# 2_BLE-T3-matrix.net
KiCad netlist of a schematic drawn in Altium Designer
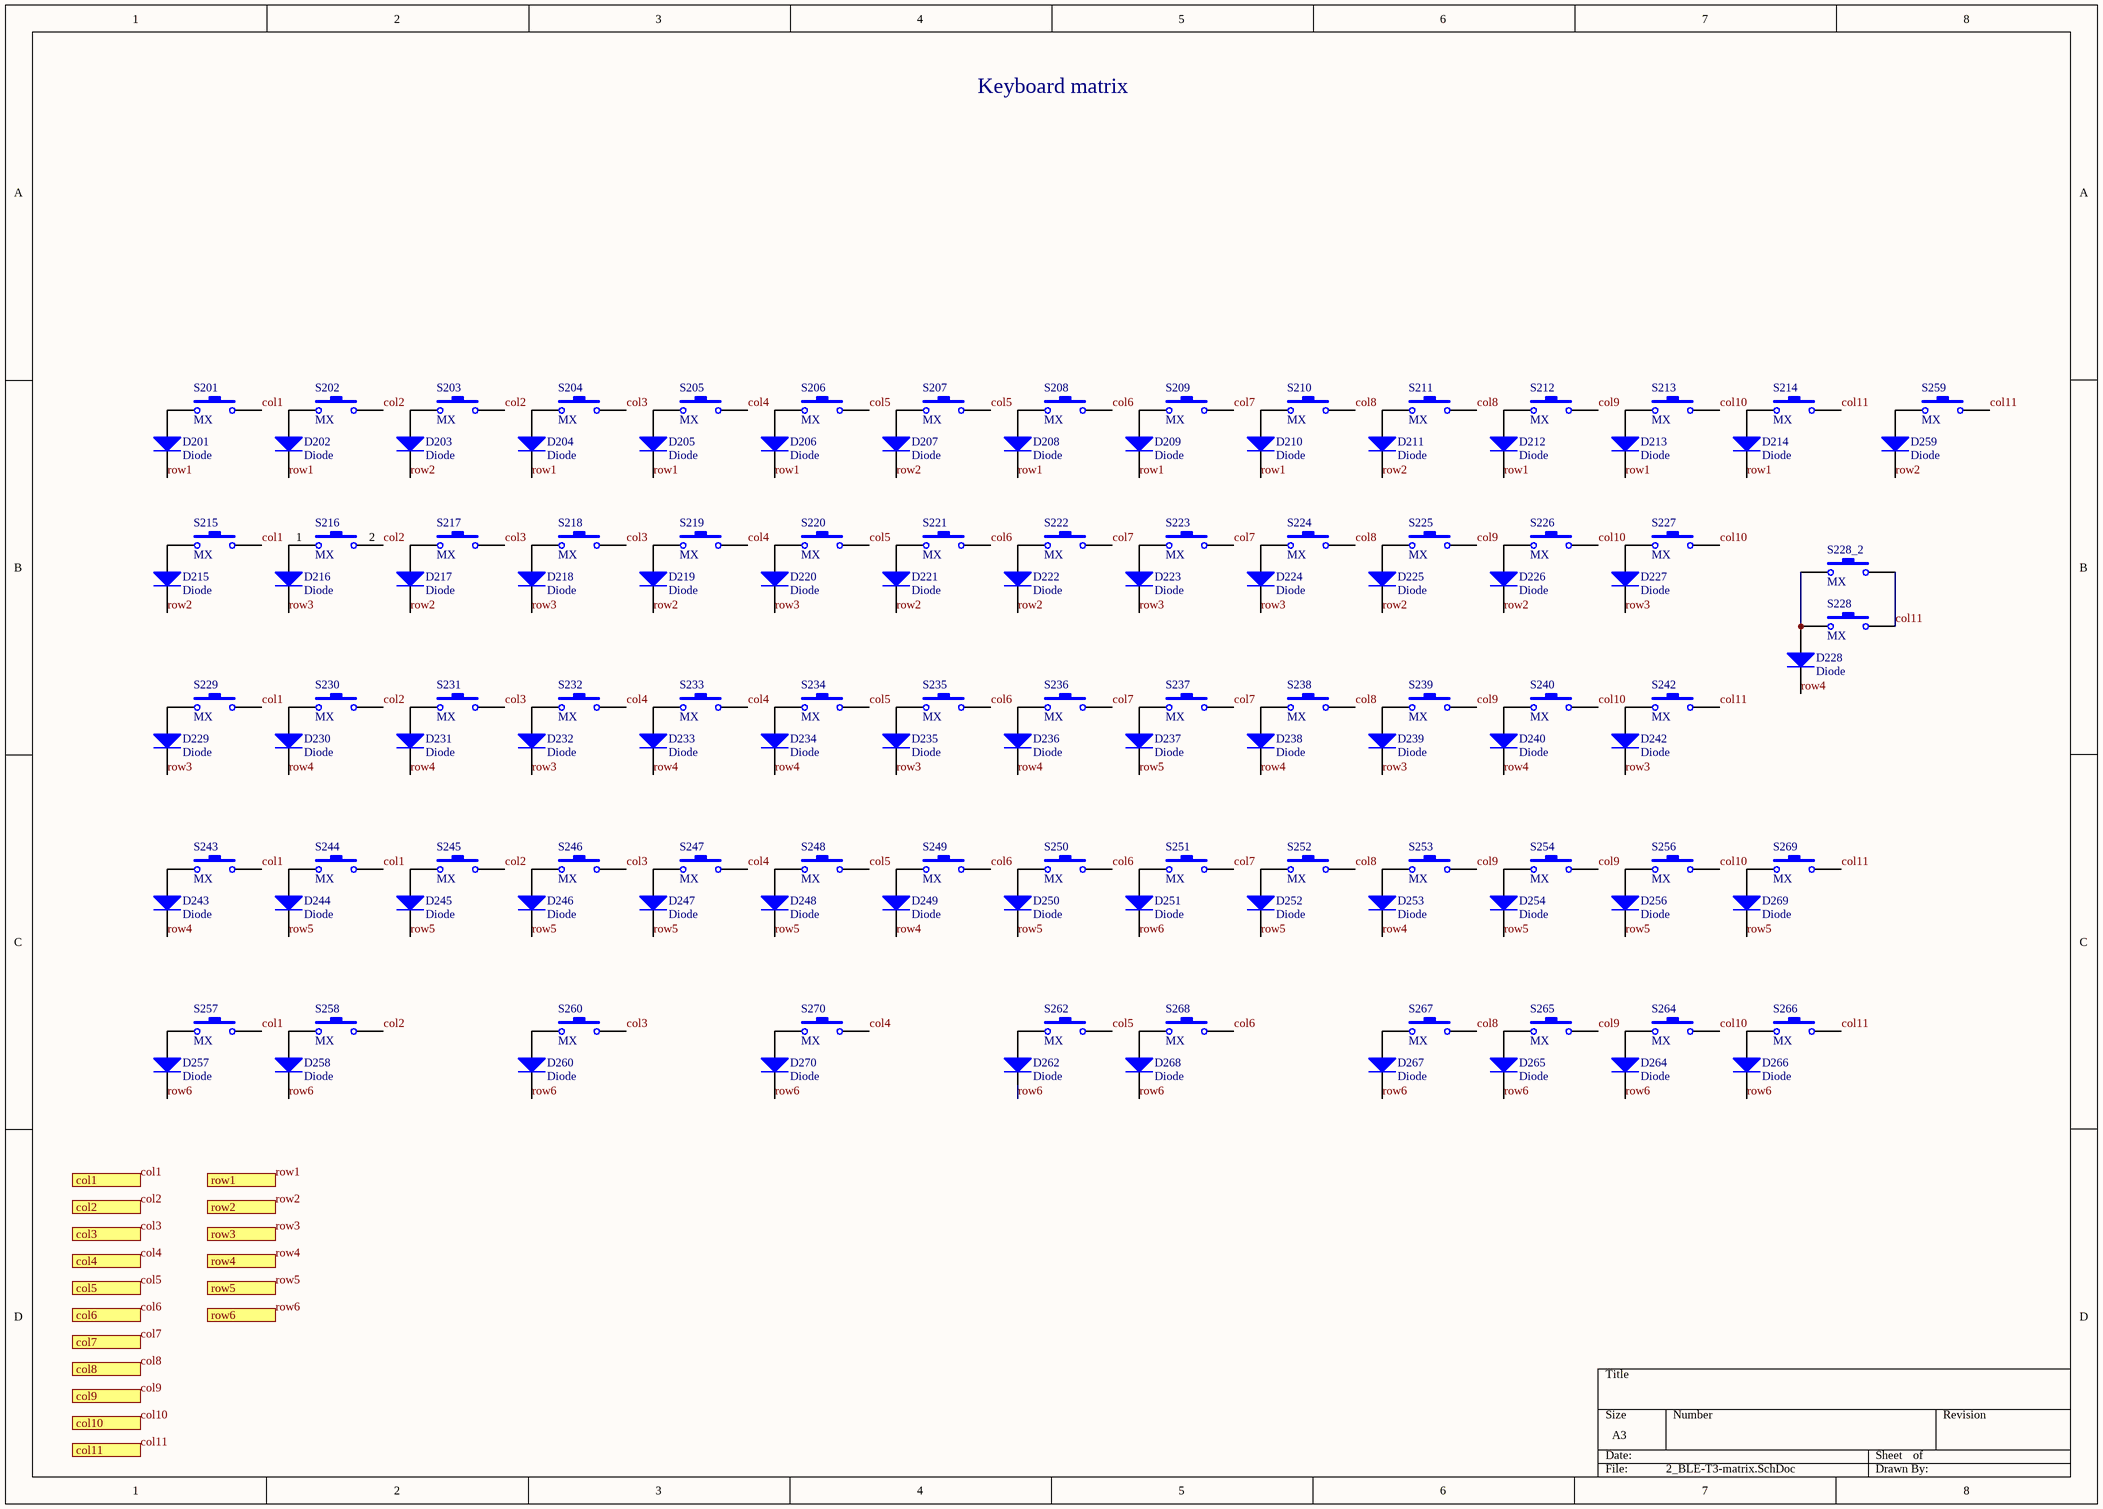
[diagram p0: 2_BLE-T3-matrix.SchDoc]

(export (version "E")
  (design (tool "Eeschema 10.0.6"))
  (components
    (comp (ref "D201")
      (value "Diode")
      (footprint "SOD-123")
      (description "Default Diode")
      (fields (field (name "MFG") "Bourns Inc.") (field (name "LCSC PART #") "C109002"))
      (libsource (lib "Miscellaneous Devices") (part "Diode"))
    )
    (comp (ref "D202")
      (value "Diode")
      (footprint "SOD-123")
      (description "Default Diode")
      (fields (field (name "MFG") "Bourns Inc.") (field (name "LCSC PART #") "C109002"))
      (libsource (lib "Miscellaneous Devices") (part "Diode"))
    )
    (comp (ref "D203")
      (value "Diode")
      (footprint "SOD-123")
      (description "Default Diode")
      (fields (field (name "MFG") "Bourns Inc.") (field (name "LCSC PART #") "C109002"))
      (libsource (lib "Miscellaneous Devices") (part "Diode"))
    )
    (comp (ref "D204")
      (value "Diode")
      (footprint "SOD-123")
      (description "Default Diode")
      (fields (field (name "MFG") "Bourns Inc.") (field (name "LCSC PART #") "C109002"))
      (libsource (lib "Miscellaneous Devices") (part "Diode"))
    )
    (comp (ref "D205")
      (value "Diode")
      (footprint "SOD-123")
      (description "Default Diode")
      (fields (field (name "MFG") "Bourns Inc.") (field (name "LCSC PART #") "C109002"))
      (libsource (lib "Miscellaneous Devices") (part "Diode"))
    )
    (comp (ref "D206")
      (value "Diode")
      (footprint "SOD-123")
      (description "Default Diode")
      (fields (field (name "MFG") "Bourns Inc.") (field (name "LCSC PART #") "C109002"))
      (libsource (lib "Miscellaneous Devices") (part "Diode"))
    )
    (comp (ref "D207")
      (value "Diode")
      (footprint "SOD-123")
      (description "Default Diode")
      (fields (field (name "MFG") "Bourns Inc.") (field (name "LCSC PART #") "C109002"))
      (libsource (lib "Miscellaneous Devices") (part "Diode"))
    )
    (comp (ref "D208")
      (value "Diode")
      (footprint "SOD-123")
      (description "Default Diode")
      (fields (field (name "MFG") "Bourns Inc.") (field (name "LCSC PART #") "C109002"))
      (libsource (lib "Miscellaneous Devices") (part "Diode"))
    )
    (comp (ref "D209")
      (value "Diode")
      (footprint "SOD-123")
      (description "Default Diode")
      (fields (field (name "MFG") "Bourns Inc.") (field (name "LCSC PART #") "C109002"))
      (libsource (lib "Miscellaneous Devices") (part "Diode"))
    )
    (comp (ref "D210")
      (value "Diode")
      (footprint "SOD-123")
      (description "Default Diode")
      (fields (field (name "MFG") "Bourns Inc.") (field (name "LCSC PART #") "C109002"))
      (libsource (lib "Miscellaneous Devices") (part "Diode"))
    )
    (comp (ref "D211")
      (value "Diode")
      (footprint "SOD-123")
      (description "Default Diode")
      (fields (field (name "MFG") "Bourns Inc.") (field (name "LCSC PART #") "C109002"))
      (libsource (lib "Miscellaneous Devices") (part "Diode"))
    )
    (comp (ref "D212")
      (value "Diode")
      (footprint "SOD-123")
      (description "Default Diode")
      (fields (field (name "MFG") "Bourns Inc.") (field (name "LCSC PART #") "C109002"))
      (libsource (lib "Miscellaneous Devices") (part "Diode"))
    )
    (comp (ref "D213")
      (value "Diode")
      (footprint "SOD-123")
      (description "Default Diode")
      (fields (field (name "MFG") "Bourns Inc.") (field (name "LCSC PART #") "C109002"))
      (libsource (lib "Miscellaneous Devices") (part "Diode"))
    )
    (comp (ref "D214")
      (value "Diode")
      (footprint "SOD-123")
      (description "Default Diode")
      (fields (field (name "MFG") "Bourns Inc.") (field (name "LCSC PART #") "C109002"))
      (libsource (lib "Miscellaneous Devices") (part "Diode"))
    )
    (comp (ref "D215")
      (value "Diode")
      (footprint "SOD-123")
      (description "Default Diode")
      (fields (field (name "MFG") "Bourns Inc.") (field (name "LCSC PART #") "C109002"))
      (libsource (lib "Miscellaneous Devices") (part "Diode"))
    )
    (comp (ref "D216")
      (value "Diode")
      (footprint "SOD-123")
      (description "Default Diode")
      (fields (field (name "MFG") "Bourns Inc.") (field (name "LCSC PART #") "C109002"))
      (libsource (lib "Miscellaneous Devices") (part "Diode"))
    )
    (comp (ref "D217")
      (value "Diode")
      (footprint "SOD-123")
      (description "Default Diode")
      (fields (field (name "MFG") "Bourns Inc.") (field (name "LCSC PART #") "C109002"))
      (libsource (lib "Miscellaneous Devices") (part "Diode"))
    )
    (comp (ref "D218")
      (value "Diode")
      (footprint "SOD-123")
      (description "Default Diode")
      (fields (field (name "MFG") "Bourns Inc.") (field (name "LCSC PART #") "C109002"))
      (libsource (lib "Miscellaneous Devices") (part "Diode"))
    )
    (comp (ref "D219")
      (value "Diode")
      (footprint "SOD-123")
      (description "Default Diode")
      (fields (field (name "MFG") "Bourns Inc.") (field (name "LCSC PART #") "C109002"))
      (libsource (lib "Miscellaneous Devices") (part "Diode"))
    )
    (comp (ref "D220")
      (value "Diode")
      (footprint "SOD-123")
      (description "Default Diode")
      (fields (field (name "MFG") "Bourns Inc.") (field (name "LCSC PART #") "C109002"))
      (libsource (lib "Miscellaneous Devices") (part "Diode"))
    )
    (comp (ref "D221")
      (value "Diode")
      (footprint "SOD-123")
      (description "Default Diode")
      (fields (field (name "MFG") "Bourns Inc.") (field (name "LCSC PART #") "C109002"))
      (libsource (lib "Miscellaneous Devices") (part "Diode"))
    )
    (comp (ref "D222")
      (value "Diode")
      (footprint "SOD-123")
      (description "Default Diode")
      (fields (field (name "MFG") "Bourns Inc.") (field (name "LCSC PART #") "C109002"))
      (libsource (lib "Miscellaneous Devices") (part "Diode"))
    )
    (comp (ref "D223")
      (value "Diode")
      (footprint "SOD-123")
      (description "Default Diode")
      (fields (field (name "MFG") "Bourns Inc.") (field (name "LCSC PART #") "C109002"))
      (libsource (lib "Miscellaneous Devices") (part "Diode"))
    )
    (comp (ref "D224")
      (value "Diode")
      (footprint "SOD-123")
      (description "Default Diode")
      (fields (field (name "MFG") "Bourns Inc.") (field (name "LCSC PART #") "C109002"))
      (libsource (lib "Miscellaneous Devices") (part "Diode"))
    )
    (comp (ref "D225")
      (value "Diode")
      (footprint "SOD-123")
      (description "Default Diode")
      (fields (field (name "MFG") "Bourns Inc.") (field (name "LCSC PART #") "C109002"))
      (libsource (lib "Miscellaneous Devices") (part "Diode"))
    )
    (comp (ref "D226")
      (value "Diode")
      (footprint "SOD-123")
      (description "Default Diode")
      (fields (field (name "MFG") "Bourns Inc.") (field (name "LCSC PART #") "C109002"))
      (libsource (lib "Miscellaneous Devices") (part "Diode"))
    )
    (comp (ref "D227")
      (value "Diode")
      (footprint "SOD-123")
      (description "Default Diode")
      (fields (field (name "MFG") "Bourns Inc.") (field (name "LCSC PART #") "C109002"))
      (libsource (lib "Miscellaneous Devices") (part "Diode"))
    )
    (comp (ref "D228")
      (value "Diode")
      (footprint "SOD-123")
      (description "Default Diode")
      (fields (field (name "MFG") "Bourns Inc.") (field (name "LCSC PART #") "C109002"))
      (libsource (lib "Miscellaneous Devices") (part "Diode"))
    )
    (comp (ref "D229")
      (value "Diode")
      (footprint "SOD-123")
      (description "Default Diode")
      (fields (field (name "MFG") "Bourns Inc.") (field (name "LCSC PART #") "C109002"))
      (libsource (lib "Miscellaneous Devices") (part "Diode"))
    )
    (comp (ref "D230")
      (value "Diode")
      (footprint "SOD-123")
      (description "Default Diode")
      (fields (field (name "MFG") "Bourns Inc.") (field (name "LCSC PART #") "C109002"))
      (libsource (lib "Miscellaneous Devices") (part "Diode"))
    )
    (comp (ref "D231")
      (value "Diode")
      (footprint "SOD-123")
      (description "Default Diode")
      (fields (field (name "MFG") "Bourns Inc.") (field (name "LCSC PART #") "C109002"))
      (libsource (lib "Miscellaneous Devices") (part "Diode"))
    )
    (comp (ref "D232")
      (value "Diode")
      (footprint "SOD-123")
      (description "Default Diode")
      (fields (field (name "MFG") "Bourns Inc.") (field (name "LCSC PART #") "C109002"))
      (libsource (lib "Miscellaneous Devices") (part "Diode"))
    )
    (comp (ref "D233")
      (value "Diode")
      (footprint "SOD-123")
      (description "Default Diode")
      (fields (field (name "MFG") "Bourns Inc.") (field (name "LCSC PART #") "C109002"))
      (libsource (lib "Miscellaneous Devices") (part "Diode"))
    )
    (comp (ref "D234")
      (value "Diode")
      (footprint "SOD-123")
      (description "Default Diode")
      (fields (field (name "MFG") "Bourns Inc.") (field (name "LCSC PART #") "C109002"))
      (libsource (lib "Miscellaneous Devices") (part "Diode"))
    )
    (comp (ref "D235")
      (value "Diode")
      (footprint "SOD-123")
      (description "Default Diode")
      (fields (field (name "MFG") "Bourns Inc.") (field (name "LCSC PART #") "C109002"))
      (libsource (lib "Miscellaneous Devices") (part "Diode"))
    )
    (comp (ref "D236")
      (value "Diode")
      (footprint "SOD-123")
      (description "Default Diode")
      (fields (field (name "MFG") "Bourns Inc.") (field (name "LCSC PART #") "C109002"))
      (libsource (lib "Miscellaneous Devices") (part "Diode"))
    )
    (comp (ref "D237")
      (value "Diode")
      (footprint "SOD-123")
      (description "Default Diode")
      (fields (field (name "MFG") "Bourns Inc.") (field (name "LCSC PART #") "C109002"))
      (libsource (lib "Miscellaneous Devices") (part "Diode"))
    )
    (comp (ref "D238")
      (value "Diode")
      (footprint "SOD-123")
      (description "Default Diode")
      (fields (field (name "MFG") "Bourns Inc.") (field (name "LCSC PART #") "C109002"))
      (libsource (lib "Miscellaneous Devices") (part "Diode"))
    )
    (comp (ref "D239")
      (value "Diode")
      (footprint "SOD-123")
      (description "Default Diode")
      (fields (field (name "MFG") "Bourns Inc.") (field (name "LCSC PART #") "C109002"))
      (libsource (lib "Miscellaneous Devices") (part "Diode"))
    )
    (comp (ref "D240")
      (value "Diode")
      (footprint "SOD-123")
      (description "Default Diode")
      (fields (field (name "MFG") "Bourns Inc.") (field (name "LCSC PART #") "C109002"))
      (libsource (lib "Miscellaneous Devices") (part "Diode"))
    )
    (comp (ref "D242")
      (value "Diode")
      (footprint "SOD-123")
      (description "Default Diode")
      (fields (field (name "MFG") "Bourns Inc.") (field (name "LCSC PART #") "C109002"))
      (libsource (lib "Miscellaneous Devices") (part "Diode"))
    )
    (comp (ref "D243")
      (value "Diode")
      (footprint "SOD-123")
      (description "Default Diode")
      (fields (field (name "MFG") "Bourns Inc.") (field (name "LCSC PART #") "C109002"))
      (libsource (lib "Miscellaneous Devices") (part "Diode"))
    )
    (comp (ref "D244")
      (value "Diode")
      (footprint "SOD-123")
      (description "Default Diode")
      (fields (field (name "MFG") "Bourns Inc.") (field (name "LCSC PART #") "C109002"))
      (libsource (lib "Miscellaneous Devices") (part "Diode"))
    )
    (comp (ref "D245")
      (value "Diode")
      (footprint "SOD-123")
      (description "Default Diode")
      (fields (field (name "MFG") "Bourns Inc.") (field (name "LCSC PART #") "C109002"))
      (libsource (lib "Miscellaneous Devices") (part "Diode"))
    )
    (comp (ref "D246")
      (value "Diode")
      (footprint "SOD-123")
      (description "Default Diode")
      (fields (field (name "MFG") "Bourns Inc.") (field (name "LCSC PART #") "C109002"))
      (libsource (lib "Miscellaneous Devices") (part "Diode"))
    )
    (comp (ref "D247")
      (value "Diode")
      (footprint "SOD-123")
      (description "Default Diode")
      (fields (field (name "MFG") "Bourns Inc.") (field (name "LCSC PART #") "C109002"))
      (libsource (lib "Miscellaneous Devices") (part "Diode"))
    )
    (comp (ref "D248")
      (value "Diode")
      (footprint "SOD-123")
      (description "Default Diode")
      (fields (field (name "MFG") "Bourns Inc.") (field (name "LCSC PART #") "C109002"))
      (libsource (lib "Miscellaneous Devices") (part "Diode"))
    )
    (comp (ref "D249")
      (value "Diode")
      (footprint "SOD-123")
      (description "Default Diode")
      (fields (field (name "MFG") "Bourns Inc.") (field (name "LCSC PART #") "C109002"))
      (libsource (lib "Miscellaneous Devices") (part "Diode"))
    )
    (comp (ref "D250")
      (value "Diode")
      (footprint "SOD-123")
      (description "Default Diode")
      (fields (field (name "MFG") "Bourns Inc.") (field (name "LCSC PART #") "C109002"))
      (libsource (lib "Miscellaneous Devices") (part "Diode"))
    )
    (comp (ref "D251")
      (value "Diode")
      (footprint "SOD-123")
      (description "Default Diode")
      (fields (field (name "MFG") "Bourns Inc.") (field (name "LCSC PART #") "C109002"))
      (libsource (lib "Miscellaneous Devices") (part "Diode"))
    )
    (comp (ref "D252")
      (value "Diode")
      (footprint "SOD-123")
      (description "Default Diode")
      (fields (field (name "MFG") "Bourns Inc.") (field (name "LCSC PART #") "C109002"))
      (libsource (lib "Miscellaneous Devices") (part "Diode"))
    )
    (comp (ref "D253")
      (value "Diode")
      (footprint "SOD-123")
      (description "Default Diode")
      (fields (field (name "MFG") "Bourns Inc.") (field (name "LCSC PART #") "C109002"))
      (libsource (lib "Miscellaneous Devices") (part "Diode"))
    )
    (comp (ref "D254")
      (value "Diode")
      (footprint "SOD-123")
      (description "Default Diode")
      (fields (field (name "MFG") "Bourns Inc.") (field (name "LCSC PART #") "C109002"))
      (libsource (lib "Miscellaneous Devices") (part "Diode"))
    )
    (comp (ref "D256")
      (value "Diode")
      (footprint "SOD-123")
      (description "Default Diode")
      (fields (field (name "MFG") "Bourns Inc.") (field (name "LCSC PART #") "C109002"))
      (libsource (lib "Miscellaneous Devices") (part "Diode"))
    )
    (comp (ref "D257")
      (value "Diode")
      (footprint "SOD-123")
      (description "Default Diode")
      (fields (field (name "MFG") "Bourns Inc.") (field (name "LCSC PART #") "C109002"))
      (libsource (lib "Miscellaneous Devices") (part "Diode"))
    )
    (comp (ref "D258")
      (value "Diode")
      (footprint "SOD-123")
      (description "Default Diode")
      (fields (field (name "MFG") "Bourns Inc.") (field (name "LCSC PART #") "C109002"))
      (libsource (lib "Miscellaneous Devices") (part "Diode"))
    )
    (comp (ref "D259")
      (value "Diode")
      (footprint "SOD-123")
      (description "Default Diode")
      (fields (field (name "MFG") "Bourns Inc.") (field (name "LCSC PART #") "C109002"))
      (libsource (lib "Miscellaneous Devices") (part "Diode"))
    )
    (comp (ref "D260")
      (value "Diode")
      (footprint "SOD-123")
      (description "Default Diode")
      (fields (field (name "MFG") "Bourns Inc.") (field (name "LCSC PART #") "C109002"))
      (libsource (lib "Miscellaneous Devices") (part "Diode"))
    )
    (comp (ref "D262")
      (value "Diode")
      (footprint "SOD-123")
      (description "Default Diode")
      (fields (field (name "MFG") "Bourns Inc.") (field (name "LCSC PART #") "C109002"))
      (libsource (lib "Miscellaneous Devices") (part "Diode"))
    )
    (comp (ref "D264")
      (value "Diode")
      (footprint "SOD-123")
      (description "Default Diode")
      (fields (field (name "MFG") "Bourns Inc.") (field (name "LCSC PART #") "C109002"))
      (libsource (lib "Miscellaneous Devices") (part "Diode"))
    )
    (comp (ref "D265")
      (value "Diode")
      (footprint "SOD-123")
      (description "Default Diode")
      (fields (field (name "MFG") "Bourns Inc.") (field (name "LCSC PART #") "C109002"))
      (libsource (lib "Miscellaneous Devices") (part "Diode"))
    )
    (comp (ref "D266")
      (value "Diode")
      (footprint "SOD-123")
      (description "Default Diode")
      (fields (field (name "MFG") "Bourns Inc.") (field (name "LCSC PART #") "C109002"))
      (libsource (lib "Miscellaneous Devices") (part "Diode"))
    )
    (comp (ref "D267")
      (value "Diode")
      (footprint "SOD-123")
      (description "Default Diode")
      (fields (field (name "MFG") "Bourns Inc.") (field (name "LCSC PART #") "C109002"))
      (libsource (lib "Miscellaneous Devices") (part "Diode"))
    )
    (comp (ref "D268")
      (value "Diode")
      (footprint "SOD-123")
      (description "Default Diode")
      (fields (field (name "MFG") "Bourns Inc.") (field (name "LCSC PART #") "C109002"))
      (libsource (lib "Miscellaneous Devices") (part "Diode"))
    )
    (comp (ref "D269")
      (value "Diode")
      (footprint "SOD-123")
      (description "Default Diode")
      (fields (field (name "MFG") "Bourns Inc.") (field (name "LCSC PART #") "C109002"))
      (libsource (lib "Miscellaneous Devices") (part "Diode"))
    )
    (comp (ref "D270")
      (value "Diode")
      (footprint "SOD-123")
      (description "Default Diode")
      (fields (field (name "MFG") "Bourns Inc.") (field (name "LCSC PART #") "C109002"))
      (libsource (lib "Miscellaneous Devices") (part "Diode"))
    )
    (comp (ref "S201")
      (value "MX")
      (footprint "MX-switch - switched pol")
      (description "Switch")
      (libsource (lib "Miscellaneous Devices") (part "SW-PB"))
    )
    (comp (ref "S202")
      (value "MX")
      (footprint "MX-switch - switched pol - connector")
      (description "Switch")
      (libsource (lib "Miscellaneous Devices") (part "SW-PB"))
    )
    (comp (ref "S203")
      (value "MX")
      (footprint "MX-switch - switched pol")
      (description "Switch")
      (libsource (lib "Miscellaneous Devices") (part "SW-PB"))
    )
    (comp (ref "S204")
      (value "MX")
      (footprint "MX-switch")
      (description "Switch")
      (libsource (lib "Miscellaneous Devices") (part "SW-PB"))
    )
    (comp (ref "S205")
      (value "MX")
      (footprint "MX-switch - switched pol")
      (description "Switch")
      (libsource (lib "Miscellaneous Devices") (part "SW-PB"))
    )
    (comp (ref "S206")
      (value "MX")
      (footprint "MX-switch - switched pol")
      (description "Switch")
      (libsource (lib "Miscellaneous Devices") (part "SW-PB"))
    )
    (comp (ref "S207")
      (value "MX")
      (footprint "MX-switch - switched pol")
      (description "Switch")
      (libsource (lib "Miscellaneous Devices") (part "SW-PB"))
    )
    (comp (ref "S208")
      (value "MX")
      (footprint "MX-switch - switched pol")
      (description "Switch")
      (libsource (lib "Miscellaneous Devices") (part "SW-PB"))
    )
    (comp (ref "S209")
      (value "MX")
      (footprint "MX-switch - switched pol")
      (description "Switch")
      (libsource (lib "Miscellaneous Devices") (part "SW-PB"))
    )
    (comp (ref "S210")
      (value "MX")
      (footprint "MX-switch - switched pol")
      (description "Switch")
      (libsource (lib "Miscellaneous Devices") (part "SW-PB"))
    )
    (comp (ref "S211")
      (value "MX")
      (footprint "MX-switch - switched pol")
      (description "Switch")
      (libsource (lib "Miscellaneous Devices") (part "SW-PB"))
    )
    (comp (ref "S212")
      (value "MX")
      (footprint "MX-switch - switched pol")
      (description "Switch")
      (libsource (lib "Miscellaneous Devices") (part "SW-PB"))
    )
    (comp (ref "S213")
      (value "MX")
      (footprint "MX-switch - switched pol")
      (description "Switch")
      (libsource (lib "Miscellaneous Devices") (part "SW-PB"))
    )
    (comp (ref "S214")
      (value "MX")
      (footprint "MX-switch - switched pol")
      (description "Switch")
      (libsource (lib "Miscellaneous Devices") (part "SW-PB"))
    )
    (comp (ref "S215")
      (value "MX")
      (footprint "MX-switch - 1.5U - switched pol")
      (description "TAB")
      (libsource (lib "Miscellaneous Devices") (part "SW-PB"))
    )
    (comp (ref "S216")
      (value "MX")
      (footprint "MX-switch - switched pol")
      (description "Switch")
      (libsource (lib "") (part "SW-PB_1"))
    )
    (comp (ref "S217")
      (value "MX")
      (footprint "MX-switch - switched pol")
      (description "Switch")
      (libsource (lib "Miscellaneous Devices") (part "SW-PB"))
    )
    (comp (ref "S218")
      (value "MX")
      (footprint "MX-switch - switched pol")
      (description "Switch")
      (libsource (lib "Miscellaneous Devices") (part "SW-PB"))
    )
    (comp (ref "S219")
      (value "MX")
      (footprint "MX-switch - switched pol")
      (description "Switch")
      (libsource (lib "Miscellaneous Devices") (part "SW-PB"))
    )
    (comp (ref "S220")
      (value "MX")
      (footprint "MX-switch")
      (description "Switch")
      (libsource (lib "Miscellaneous Devices") (part "SW-PB"))
    )
    (comp (ref "S221")
      (value "MX")
      (footprint "MX-switch - switched pol")
      (description "Switch")
      (libsource (lib "Miscellaneous Devices") (part "SW-PB"))
    )
    (comp (ref "S222")
      (value "MX")
      (footprint "MX-switch - switched pol")
      (description "Switch")
      (libsource (lib "Miscellaneous Devices") (part "SW-PB"))
    )
    (comp (ref "S223")
      (value "MX")
      (footprint "MX-switch - switched pol")
      (description "Switch")
      (libsource (lib "Miscellaneous Devices") (part "SW-PB"))
    )
    (comp (ref "S224")
      (value "MX")
      (footprint "MX-switch - switched pol")
      (description "Switch")
      (libsource (lib "Miscellaneous Devices") (part "SW-PB"))
    )
    (comp (ref "S225")
      (value "MX")
      (footprint "MX-switch - switched pol")
      (description "Switch")
      (libsource (lib "Miscellaneous Devices") (part "SW-PB"))
    )
    (comp (ref "S226")
      (value "MX")
      (footprint "MX-switch")
      (description "Switch")
      (libsource (lib "Miscellaneous Devices") (part "SW-PB"))
    )
    (comp (ref "S227")
      (value "MX")
      (footprint "MX-switch")
      (description "Switch")
      (libsource (lib "Miscellaneous Devices") (part "SW-PB"))
    )
    (comp (ref "S228")
      (value "MX")
      (footprint "MX-switch - 1.5U")
      (description "Switch")
      (libsource (lib "Miscellaneous Devices") (part "SW-PB"))
    )
    (comp (ref "S228_2")
      (value "MX")
      (footprint "MX-switch")
      (description "Switch")
      (libsource (lib "Miscellaneous Devices") (part "SW-PB"))
    )
    (comp (ref "S229")
      (value "MX")
      (footprint "MX-switch - CAPS")
      (description "Switch")
      (libsource (lib "Miscellaneous Devices") (part "SW-PB"))
    )
    (comp (ref "S230")
      (value "MX")
      (footprint "MX-switch - switched pol")
      (description "Switch")
      (libsource (lib "Miscellaneous Devices") (part "SW-PB"))
    )
    (comp (ref "S231")
      (value "MX")
      (footprint "MX-switch - switched pol")
      (description "Switch")
      (libsource (lib "Miscellaneous Devices") (part "SW-PB"))
    )
    (comp (ref "S232")
      (value "MX")
      (footprint "MX-switch - switched pol")
      (description "Switch")
      (libsource (lib "Miscellaneous Devices") (part "SW-PB"))
    )
    (comp (ref "S233")
      (value "MX")
      (footprint "MX-switch - switched pol")
      (description "Switch")
      (libsource (lib "Miscellaneous Devices") (part "SW-PB"))
    )
    (comp (ref "S234")
      (value "MX")
      (footprint "MX-switch")
      (description "Switch")
      (libsource (lib "Miscellaneous Devices") (part "SW-PB"))
    )
    (comp (ref "S235")
      (value "MX")
      (footprint "MX-switch - switched pol")
      (description "Switch")
      (libsource (lib "Miscellaneous Devices") (part "SW-PB"))
    )
    (comp (ref "S236")
      (value "MX")
      (footprint "MX-switch - switched pol")
      (description "Switch")
      (libsource (lib "Miscellaneous Devices") (part "SW-PB"))
    )
    (comp (ref "S237")
      (value "MX")
      (footprint "MX-switch - switched pol")
      (description "Switch")
      (libsource (lib "Miscellaneous Devices") (part "SW-PB"))
    )
    (comp (ref "S238")
      (value "MX")
      (footprint "MX-switch - switched pol")
      (description "Switch")
      (libsource (lib "Miscellaneous Devices") (part "SW-PB"))
    )
    (comp (ref "S239")
      (value "MX")
      (footprint "MX-switch")
      (description "Switch")
      (libsource (lib "Miscellaneous Devices") (part "SW-PB"))
    )
    (comp (ref "S240")
      (value "MX")
      (footprint "MX-switch - switched pol")
      (description "Switch")
      (libsource (lib "Miscellaneous Devices") (part "SW-PB"))
    )
    (comp (ref "S242")
      (value "MX")
      (footprint "MX-switch - Enter")
      (description "Switch")
      (libsource (lib "Miscellaneous Devices") (part "SW-PB"))
    )
    (comp (ref "S243")
      (value "MX")
      (footprint "MX-switch - Left shift")
      (description "Switch")
      (libsource (lib "Miscellaneous Devices") (part "SW-PB"))
    )
    (comp (ref "S244")
      (value "MX")
      (footprint "MX-switch - switched pol")
      (description "Switch")
      (libsource (lib "Miscellaneous Devices") (part "SW-PB"))
    )
    (comp (ref "S245")
      (value "MX")
      (footprint "MX-switch - switched pol")
      (description "Switch")
      (libsource (lib "Miscellaneous Devices") (part "SW-PB"))
    )
    (comp (ref "S246")
      (value "MX")
      (footprint "MX-switch - switched pol")
      (description "Switch")
      (libsource (lib "Miscellaneous Devices") (part "SW-PB"))
    )
    (comp (ref "S247")
      (value "MX")
      (footprint "MX-switch - switched pol")
      (description "Switch")
      (libsource (lib "Miscellaneous Devices") (part "SW-PB"))
    )
    (comp (ref "S248")
      (value "MX")
      (footprint "MX-switch")
      (description "Switch")
      (libsource (lib "Miscellaneous Devices") (part "SW-PB"))
    )
    (comp (ref "S249")
      (value "MX")
      (footprint "MX-switch - switched pol")
      (description "Switch")
      (libsource (lib "Miscellaneous Devices") (part "SW-PB"))
    )
    (comp (ref "S250")
      (value "MX")
      (footprint "MX-switch - switched pol")
      (description "Switch")
      (libsource (lib "Miscellaneous Devices") (part "SW-PB"))
    )
    (comp (ref "S251")
      (value "MX")
      (footprint "MX-switch - switched pol")
      (description "Switch")
      (libsource (lib "Miscellaneous Devices") (part "SW-PB"))
    )
    (comp (ref "S252")
      (value "MX")
      (footprint "MX-switch - switched pol")
      (description "Switch")
      (libsource (lib "Miscellaneous Devices") (part "SW-PB"))
    )
    (comp (ref "S253")
      (value "MX")
      (footprint "MX-switch - switched pol")
      (description "Switch")
      (libsource (lib "Miscellaneous Devices") (part "SW-PB"))
    )
    (comp (ref "S254")
      (value "MX")
      (footprint "MX-switch - switched pol")
      (description "Switch")
      (libsource (lib "Miscellaneous Devices") (part "SW-PB"))
    )
    (comp (ref "S256")
      (value "MX")
      (footprint "MX-switch - right shift")
      (description "Switch")
      (libsource (lib "Miscellaneous Devices") (part "SW-PB"))
    )
    (comp (ref "S257")
      (value "MX")
      (footprint "MX-switch - 1.5u MOD-L")
      (description "Switch")
      (libsource (lib "Miscellaneous Devices") (part "SW-PB"))
    )
    (comp (ref "S258")
      (value "MX")
      (footprint "MX-switch - 1u MOD-L")
      (description "Switch")
      (libsource (lib "Miscellaneous Devices") (part "SW-PB"))
    )
    (comp (ref "S259")
      (value "MX")
      (footprint "MX-switch - backspace")
      (description "Switch")
      (libsource (lib "Miscellaneous Devices") (part "SW-PB"))
    )
    (comp (ref "S260")
      (value "MX")
      (footprint "MX-switch - 1.5u MOD-L")
      (description "Switch")
      (libsource (lib "Miscellaneous Devices") (part "SW-PB"))
    )
    (comp (ref "S262")
      (value "MX")
      (footprint "MX-switch - Space_V3")
      (description "Switch")
      (libsource (lib "Miscellaneous Devices") (part "SW-PB"))
    )
    (comp (ref "S264")
      (value "MX")
      (footprint "MX-switch - 1u MOD-R")
      (description "Switch")
      (libsource (lib "Miscellaneous Devices") (part "SW-PB"))
    )
    (comp (ref "S265")
      (value "MX")
      (footprint "MX-switch - 1.5u MOD-R")
      (description "Switch")
      (libsource (lib "Miscellaneous Devices") (part "SW-PB"))
    )
    (comp (ref "S266")
      (value "MX")
      (footprint "MX-switch - 1.5u MOD-R")
      (description "Switch")
      (libsource (lib "Miscellaneous Devices") (part "SW-PB"))
    )
    (comp (ref "S267")
      (value "MX")
      (footprint "MX-switch - switched pol")
      (description "Switch")
      (libsource (lib "Miscellaneous Devices") (part "SW-PB"))
    )
    (comp (ref "S268")
      (value "MX")
      (footprint "MX-switch - R split space_V2")
      (description "Switch")
      (libsource (lib "Miscellaneous Devices") (part "SW-PB"))
    )
    (comp (ref "S269")
      (value "MX")
      (footprint "MX-switch")
      (description "Switch")
      (libsource (lib "Miscellaneous Devices") (part "SW-PB"))
    )
    (comp (ref "S270")
      (value "MX")
      (footprint "MX-switch - L split space_V2")
      (description "Switch")
      (libsource (lib "Miscellaneous Devices") (part "SW-PB"))
    )
  )
  (nets
    (net (code "1") (name "/col1") (class "Default")
      (node (ref "S201") (pin "2") (pinfunction "2_2") (pintype "passive"))
      (node (ref "S215") (pin "2") (pinfunction "2_2") (pintype "passive"))
      (node (ref "S229") (pin "2") (pinfunction "2_2") (pintype "passive"))
      (node (ref "S243") (pin "2") (pinfunction "2_2") (pintype "passive"))
      (node (ref "S244") (pin "2") (pinfunction "2_2") (pintype "passive"))
      (node (ref "S257") (pin "2") (pinfunction "2_2") (pintype "passive"))
    )
    (net (code "2") (name "/col2") (class "Default")
      (node (ref "S202") (pin "2") (pinfunction "2_2") (pintype "passive"))
      (node (ref "S203") (pin "2") (pinfunction "2_2") (pintype "passive"))
      (node (ref "S216") (pin "2") (pinfunction "2_2") (pintype "passive"))
      (node (ref "S230") (pin "2") (pinfunction "2_2") (pintype "passive"))
      (node (ref "S245") (pin "2") (pinfunction "2_2") (pintype "passive"))
      (node (ref "S258") (pin "2") (pinfunction "2_2") (pintype "passive"))
    )
    (net (code "3") (name "/col3") (class "Default")
      (node (ref "S204") (pin "2") (pinfunction "2_2") (pintype "passive"))
      (node (ref "S217") (pin "2") (pinfunction "2_2") (pintype "passive"))
      (node (ref "S218") (pin "2") (pinfunction "2_2") (pintype "passive"))
      (node (ref "S231") (pin "2") (pinfunction "2_2") (pintype "passive"))
      (node (ref "S246") (pin "2") (pinfunction "2_2") (pintype "passive"))
      (node (ref "S260") (pin "2") (pinfunction "2_2") (pintype "passive"))
    )
    (net (code "4") (name "/col4") (class "Default")
      (node (ref "S205") (pin "2") (pinfunction "2_2") (pintype "passive"))
      (node (ref "S219") (pin "2") (pinfunction "2_2") (pintype "passive"))
      (node (ref "S232") (pin "2") (pinfunction "2_2") (pintype "passive"))
      (node (ref "S233") (pin "2") (pinfunction "2_2") (pintype "passive"))
      (node (ref "S247") (pin "2") (pinfunction "2_2") (pintype "passive"))
      (node (ref "S270") (pin "2") (pinfunction "2_2") (pintype "passive"))
    )
    (net (code "5") (name "/col5") (class "Default")
      (node (ref "S206") (pin "2") (pinfunction "2_2") (pintype "passive"))
      (node (ref "S207") (pin "2") (pinfunction "2_2") (pintype "passive"))
      (node (ref "S220") (pin "2") (pinfunction "2_2") (pintype "passive"))
      (node (ref "S234") (pin "2") (pinfunction "2_2") (pintype "passive"))
      (node (ref "S248") (pin "2") (pinfunction "2_2") (pintype "passive"))
      (node (ref "S262") (pin "1") (pinfunction "1_1") (pintype "passive"))
    )
    (net (code "6") (name "/col6") (class "Default")
      (node (ref "S208") (pin "2") (pinfunction "2_2") (pintype "passive"))
      (node (ref "S221") (pin "2") (pinfunction "2_2") (pintype "passive"))
      (node (ref "S235") (pin "2") (pinfunction "2_2") (pintype "passive"))
      (node (ref "S249") (pin "2") (pinfunction "2_2") (pintype "passive"))
      (node (ref "S250") (pin "2") (pinfunction "2_2") (pintype "passive"))
      (node (ref "S268") (pin "2") (pinfunction "2_2") (pintype "passive"))
    )
    (net (code "7") (name "/col7") (class "Default")
      (node (ref "S209") (pin "2") (pinfunction "2_2") (pintype "passive"))
      (node (ref "S222") (pin "2") (pinfunction "2_2") (pintype "passive"))
      (node (ref "S223") (pin "2") (pinfunction "2_2") (pintype "passive"))
      (node (ref "S236") (pin "2") (pinfunction "2_2") (pintype "passive"))
      (node (ref "S237") (pin "2") (pinfunction "2_2") (pintype "passive"))
      (node (ref "S251") (pin "2") (pinfunction "2_2") (pintype "passive"))
    )
    (net (code "8") (name "/col8") (class "Default")
      (node (ref "S210") (pin "2") (pinfunction "2_2") (pintype "passive"))
      (node (ref "S211") (pin "2") (pinfunction "2_2") (pintype "passive"))
      (node (ref "S224") (pin "2") (pinfunction "2_2") (pintype "passive"))
      (node (ref "S238") (pin "2") (pinfunction "2_2") (pintype "passive"))
      (node (ref "S252") (pin "2") (pinfunction "2_2") (pintype "passive"))
      (node (ref "S267") (pin "2") (pinfunction "2_2") (pintype "passive"))
    )
    (net (code "9") (name "/col9") (class "Default")
      (node (ref "S212") (pin "2") (pinfunction "2_2") (pintype "passive"))
      (node (ref "S225") (pin "2") (pinfunction "2_2") (pintype "passive"))
      (node (ref "S239") (pin "2") (pinfunction "2_2") (pintype "passive"))
      (node (ref "S253") (pin "2") (pinfunction "2_2") (pintype "passive"))
      (node (ref "S254") (pin "2") (pinfunction "2_2") (pintype "passive"))
      (node (ref "S265") (pin "1") (pinfunction "1_1") (pintype "passive"))
    )
    (net (code "10") (name "/col10") (class "Default")
      (node (ref "S213") (pin "2") (pinfunction "2_2") (pintype "passive"))
      (node (ref "S226") (pin "2") (pinfunction "2_2") (pintype "passive"))
      (node (ref "S227") (pin "2") (pinfunction "2_2") (pintype "passive"))
      (node (ref "S240") (pin "2") (pinfunction "2_2") (pintype "passive"))
      (node (ref "S256") (pin "2") (pinfunction "2_2") (pintype "passive"))
      (node (ref "S264") (pin "2") (pinfunction "2_2") (pintype "passive"))
    )
    (net (code "11") (name "/col11") (class "Default")
      (node (ref "S214") (pin "2") (pinfunction "2_2") (pintype "passive"))
      (node (ref "S228") (pin "2") (pinfunction "2_2") (pintype "passive"))
      (node (ref "S228_2") (pin "2") (pinfunction "2_2") (pintype "passive"))
      (node (ref "S242") (pin "2") (pinfunction "2_2") (pintype "passive"))
      (node (ref "S259") (pin "2") (pinfunction "2_2") (pintype "passive"))
      (node (ref "S266") (pin "2") (pinfunction "2_2") (pintype "passive"))
      (node (ref "S269") (pin "2") (pinfunction "2_2") (pintype "passive"))
    )
    (net (code "12") (name "/row1") (class "Default")
      (node (ref "D201") (pin "2") (pinfunction "K_2") (pintype "passive"))
      (node (ref "D202") (pin "2") (pinfunction "K_2") (pintype "passive"))
      (node (ref "D204") (pin "2") (pinfunction "K_2") (pintype "passive"))
      (node (ref "D205") (pin "2") (pinfunction "K_2") (pintype "passive"))
      (node (ref "D206") (pin "2") (pinfunction "K_2") (pintype "passive"))
      (node (ref "D208") (pin "2") (pinfunction "K_2") (pintype "passive"))
      (node (ref "D209") (pin "2") (pinfunction "K_2") (pintype "passive"))
      (node (ref "D210") (pin "2") (pinfunction "K_2") (pintype "passive"))
      (node (ref "D212") (pin "2") (pinfunction "K_2") (pintype "passive"))
      (node (ref "D213") (pin "2") (pinfunction "K_2") (pintype "passive"))
      (node (ref "D214") (pin "2") (pinfunction "K_2") (pintype "passive"))
    )
    (net (code "13") (name "/row2") (class "Default")
      (node (ref "D203") (pin "2") (pinfunction "K_2") (pintype "passive"))
      (node (ref "D207") (pin "2") (pinfunction "K_2") (pintype "passive"))
      (node (ref "D211") (pin "2") (pinfunction "K_2") (pintype "passive"))
      (node (ref "D215") (pin "2") (pinfunction "K_2") (pintype "passive"))
      (node (ref "D217") (pin "2") (pinfunction "K_2") (pintype "passive"))
      (node (ref "D219") (pin "2") (pinfunction "K_2") (pintype "passive"))
      (node (ref "D221") (pin "2") (pinfunction "K_2") (pintype "passive"))
      (node (ref "D222") (pin "2") (pinfunction "K_2") (pintype "passive"))
      (node (ref "D225") (pin "2") (pinfunction "K_2") (pintype "passive"))
      (node (ref "D226") (pin "2") (pinfunction "K_2") (pintype "passive"))
      (node (ref "D259") (pin "2") (pinfunction "K_2") (pintype "passive"))
    )
    (net (code "14") (name "/row3") (class "Default")
      (node (ref "D216") (pin "2") (pinfunction "K_2") (pintype "passive"))
      (node (ref "D218") (pin "2") (pinfunction "K_2") (pintype "passive"))
      (node (ref "D220") (pin "2") (pinfunction "K_2") (pintype "passive"))
      (node (ref "D223") (pin "2") (pinfunction "K_2") (pintype "passive"))
      (node (ref "D224") (pin "2") (pinfunction "K_2") (pintype "passive"))
      (node (ref "D227") (pin "2") (pinfunction "K_2") (pintype "passive"))
      (node (ref "D229") (pin "2") (pinfunction "K_2") (pintype "passive"))
      (node (ref "D232") (pin "2") (pinfunction "K_2") (pintype "passive"))
      (node (ref "D235") (pin "2") (pinfunction "K_2") (pintype "passive"))
      (node (ref "D239") (pin "2") (pinfunction "K_2") (pintype "passive"))
      (node (ref "D242") (pin "2") (pinfunction "K_2") (pintype "passive"))
    )
    (net (code "15") (name "/row4") (class "Default")
      (node (ref "D228") (pin "2") (pinfunction "K_2") (pintype "passive"))
      (node (ref "D230") (pin "2") (pinfunction "K_2") (pintype "passive"))
      (node (ref "D231") (pin "2") (pinfunction "K_2") (pintype "passive"))
      (node (ref "D233") (pin "2") (pinfunction "K_2") (pintype "passive"))
      (node (ref "D234") (pin "2") (pinfunction "K_2") (pintype "passive"))
      (node (ref "D236") (pin "2") (pinfunction "K_2") (pintype "passive"))
      (node (ref "D238") (pin "2") (pinfunction "K_2") (pintype "passive"))
      (node (ref "D240") (pin "2") (pinfunction "K_2") (pintype "passive"))
      (node (ref "D243") (pin "2") (pinfunction "K_2") (pintype "passive"))
      (node (ref "D249") (pin "2") (pinfunction "K_2") (pintype "passive"))
      (node (ref "D253") (pin "2") (pinfunction "K_2") (pintype "passive"))
    )
    (net (code "16") (name "/row5") (class "Default")
      (node (ref "D237") (pin "2") (pinfunction "K_2") (pintype "passive"))
      (node (ref "D244") (pin "2") (pinfunction "K_2") (pintype "passive"))
      (node (ref "D245") (pin "2") (pinfunction "K_2") (pintype "passive"))
      (node (ref "D246") (pin "2") (pinfunction "K_2") (pintype "passive"))
      (node (ref "D247") (pin "2") (pinfunction "K_2") (pintype "passive"))
      (node (ref "D248") (pin "2") (pinfunction "K_2") (pintype "passive"))
      (node (ref "D250") (pin "2") (pinfunction "K_2") (pintype "passive"))
      (node (ref "D252") (pin "2") (pinfunction "K_2") (pintype "passive"))
      (node (ref "D254") (pin "2") (pinfunction "K_2") (pintype "passive"))
      (node (ref "D256") (pin "2") (pinfunction "K_2") (pintype "passive"))
      (node (ref "D269") (pin "2") (pinfunction "K_2") (pintype "passive"))
    )
    (net (code "17") (name "/row6") (class "Default")
      (node (ref "D251") (pin "2") (pinfunction "K_2") (pintype "passive"))
      (node (ref "D257") (pin "2") (pinfunction "K_2") (pintype "passive"))
      (node (ref "D258") (pin "2") (pinfunction "K_2") (pintype "passive"))
      (node (ref "D260") (pin "2") (pinfunction "K_2") (pintype "passive"))
      (node (ref "D262") (pin "2") (pinfunction "K_2") (pintype "passive"))
      (node (ref "D264") (pin "2") (pinfunction "K_2") (pintype "passive"))
      (node (ref "D265") (pin "2") (pinfunction "K_2") (pintype "passive"))
      (node (ref "D266") (pin "2") (pinfunction "K_2") (pintype "passive"))
      (node (ref "D267") (pin "2") (pinfunction "K_2") (pintype "passive"))
      (node (ref "D268") (pin "2") (pinfunction "K_2") (pintype "passive"))
      (node (ref "D270") (pin "2") (pinfunction "K_2") (pintype "passive"))
    )
    (net (code "18") (name "Net-(D201-A)") (class "Default")
      (node (ref "D201") (pin "1") (pinfunction "A_1") (pintype "passive"))
      (node (ref "S201") (pin "1") (pinfunction "1_1") (pintype "passive"))
    )
    (net (code "19") (name "Net-(D202-A)") (class "Default")
      (node (ref "D202") (pin "1") (pinfunction "A_1") (pintype "passive"))
      (node (ref "S202") (pin "1") (pinfunction "1_1") (pintype "passive"))
    )
    (net (code "20") (name "Net-(D203-A)") (class "Default")
      (node (ref "D203") (pin "1") (pinfunction "A_1") (pintype "passive"))
      (node (ref "S203") (pin "1") (pinfunction "1_1") (pintype "passive"))
    )
    (net (code "21") (name "Net-(D204-A)") (class "Default")
      (node (ref "D204") (pin "1") (pinfunction "A_1") (pintype "passive"))
      (node (ref "S204") (pin "1") (pinfunction "1_1") (pintype "passive"))
    )
    (net (code "22") (name "Net-(D205-A)") (class "Default")
      (node (ref "D205") (pin "1") (pinfunction "A_1") (pintype "passive"))
      (node (ref "S205") (pin "1") (pinfunction "1_1") (pintype "passive"))
    )
    (net (code "23") (name "Net-(D206-A)") (class "Default")
      (node (ref "D206") (pin "1") (pinfunction "A_1") (pintype "passive"))
      (node (ref "S206") (pin "1") (pinfunction "1_1") (pintype "passive"))
    )
    (net (code "24") (name "Net-(D207-A)") (class "Default")
      (node (ref "D207") (pin "1") (pinfunction "A_1") (pintype "passive"))
      (node (ref "S207") (pin "1") (pinfunction "1_1") (pintype "passive"))
    )
    (net (code "25") (name "Net-(D208-A)") (class "Default")
      (node (ref "D208") (pin "1") (pinfunction "A_1") (pintype "passive"))
      (node (ref "S208") (pin "1") (pinfunction "1_1") (pintype "passive"))
    )
    (net (code "26") (name "Net-(D209-A)") (class "Default")
      (node (ref "D209") (pin "1") (pinfunction "A_1") (pintype "passive"))
      (node (ref "S209") (pin "1") (pinfunction "1_1") (pintype "passive"))
    )
    (net (code "27") (name "Net-(D210-A)") (class "Default")
      (node (ref "D210") (pin "1") (pinfunction "A_1") (pintype "passive"))
      (node (ref "S210") (pin "1") (pinfunction "1_1") (pintype "passive"))
    )
    (net (code "28") (name "Net-(D211-A)") (class "Default")
      (node (ref "D211") (pin "1") (pinfunction "A_1") (pintype "passive"))
      (node (ref "S211") (pin "1") (pinfunction "1_1") (pintype "passive"))
    )
    (net (code "29") (name "Net-(D212-A)") (class "Default")
      (node (ref "D212") (pin "1") (pinfunction "A_1") (pintype "passive"))
      (node (ref "S212") (pin "1") (pinfunction "1_1") (pintype "passive"))
    )
    (net (code "30") (name "Net-(D213-A)") (class "Default")
      (node (ref "D213") (pin "1") (pinfunction "A_1") (pintype "passive"))
      (node (ref "S213") (pin "1") (pinfunction "1_1") (pintype "passive"))
    )
    (net (code "31") (name "Net-(D214-A)") (class "Default")
      (node (ref "D214") (pin "1") (pinfunction "A_1") (pintype "passive"))
      (node (ref "S214") (pin "1") (pinfunction "1_1") (pintype "passive"))
    )
    (net (code "32") (name "Net-(D215-A)") (class "Default")
      (node (ref "D215") (pin "1") (pinfunction "A_1") (pintype "passive"))
      (node (ref "S215") (pin "1") (pinfunction "1_1") (pintype "passive"))
    )
    (net (code "33") (name "Net-(D216-A)") (class "Default")
      (node (ref "D216") (pin "1") (pinfunction "A_1") (pintype "passive"))
      (node (ref "S216") (pin "1") (pinfunction "1_1") (pintype "passive"))
    )
    (net (code "34") (name "Net-(D217-A)") (class "Default")
      (node (ref "D217") (pin "1") (pinfunction "A_1") (pintype "passive"))
      (node (ref "S217") (pin "1") (pinfunction "1_1") (pintype "passive"))
    )
    (net (code "35") (name "Net-(D218-A)") (class "Default")
      (node (ref "D218") (pin "1") (pinfunction "A_1") (pintype "passive"))
      (node (ref "S218") (pin "1") (pinfunction "1_1") (pintype "passive"))
    )
    (net (code "36") (name "Net-(D219-A)") (class "Default")
      (node (ref "D219") (pin "1") (pinfunction "A_1") (pintype "passive"))
      (node (ref "S219") (pin "1") (pinfunction "1_1") (pintype "passive"))
    )
    (net (code "37") (name "Net-(D220-A)") (class "Default")
      (node (ref "D220") (pin "1") (pinfunction "A_1") (pintype "passive"))
      (node (ref "S220") (pin "1") (pinfunction "1_1") (pintype "passive"))
    )
    (net (code "38") (name "Net-(D221-A)") (class "Default")
      (node (ref "D221") (pin "1") (pinfunction "A_1") (pintype "passive"))
      (node (ref "S221") (pin "1") (pinfunction "1_1") (pintype "passive"))
    )
    (net (code "39") (name "Net-(D222-A)") (class "Default")
      (node (ref "D222") (pin "1") (pinfunction "A_1") (pintype "passive"))
      (node (ref "S222") (pin "1") (pinfunction "1_1") (pintype "passive"))
    )
    (net (code "40") (name "Net-(D223-A)") (class "Default")
      (node (ref "D223") (pin "1") (pinfunction "A_1") (pintype "passive"))
      (node (ref "S223") (pin "1") (pinfunction "1_1") (pintype "passive"))
    )
    (net (code "41") (name "Net-(D224-A)") (class "Default")
      (node (ref "D224") (pin "1") (pinfunction "A_1") (pintype "passive"))
      (node (ref "S224") (pin "1") (pinfunction "1_1") (pintype "passive"))
    )
    (net (code "42") (name "Net-(D225-A)") (class "Default")
      (node (ref "D225") (pin "1") (pinfunction "A_1") (pintype "passive"))
      (node (ref "S225") (pin "1") (pinfunction "1_1") (pintype "passive"))
    )
    (net (code "43") (name "Net-(D226-A)") (class "Default")
      (node (ref "D226") (pin "1") (pinfunction "A_1") (pintype "passive"))
      (node (ref "S226") (pin "1") (pinfunction "1_1") (pintype "passive"))
    )
    (net (code "44") (name "Net-(D227-A)") (class "Default")
      (node (ref "D227") (pin "1") (pinfunction "A_1") (pintype "passive"))
      (node (ref "S227") (pin "1") (pinfunction "1_1") (pintype "passive"))
    )
    (net (code "45") (name "Net-(D228-A)") (class "Default")
      (node (ref "D228") (pin "1") (pinfunction "A_1") (pintype "passive"))
      (node (ref "S228") (pin "1") (pinfunction "1_1") (pintype "passive"))
      (node (ref "S228_2") (pin "1") (pinfunction "1_1") (pintype "passive"))
    )
    (net (code "46") (name "Net-(D229-A)") (class "Default")
      (node (ref "D229") (pin "1") (pinfunction "A_1") (pintype "passive"))
      (node (ref "S229") (pin "1") (pinfunction "1_1") (pintype "passive"))
    )
    (net (code "47") (name "Net-(D230-A)") (class "Default")
      (node (ref "D230") (pin "1") (pinfunction "A_1") (pintype "passive"))
      (node (ref "S230") (pin "1") (pinfunction "1_1") (pintype "passive"))
    )
    (net (code "48") (name "Net-(D231-A)") (class "Default")
      (node (ref "D231") (pin "1") (pinfunction "A_1") (pintype "passive"))
      (node (ref "S231") (pin "1") (pinfunction "1_1") (pintype "passive"))
    )
    (net (code "49") (name "Net-(D232-A)") (class "Default")
      (node (ref "D232") (pin "1") (pinfunction "A_1") (pintype "passive"))
      (node (ref "S232") (pin "1") (pinfunction "1_1") (pintype "passive"))
    )
    (net (code "50") (name "Net-(D233-A)") (class "Default")
      (node (ref "D233") (pin "1") (pinfunction "A_1") (pintype "passive"))
      (node (ref "S233") (pin "1") (pinfunction "1_1") (pintype "passive"))
    )
    (net (code "51") (name "Net-(D234-A)") (class "Default")
      (node (ref "D234") (pin "1") (pinfunction "A_1") (pintype "passive"))
      (node (ref "S234") (pin "1") (pinfunction "1_1") (pintype "passive"))
    )
    (net (code "52") (name "Net-(D235-A)") (class "Default")
      (node (ref "D235") (pin "1") (pinfunction "A_1") (pintype "passive"))
      (node (ref "S235") (pin "1") (pinfunction "1_1") (pintype "passive"))
    )
    (net (code "53") (name "Net-(D236-A)") (class "Default")
      (node (ref "D236") (pin "1") (pinfunction "A_1") (pintype "passive"))
      (node (ref "S236") (pin "1") (pinfunction "1_1") (pintype "passive"))
    )
    (net (code "54") (name "Net-(D237-A)") (class "Default")
      (node (ref "D237") (pin "1") (pinfunction "A_1") (pintype "passive"))
      (node (ref "S237") (pin "1") (pinfunction "1_1") (pintype "passive"))
    )
    (net (code "55") (name "Net-(D238-A)") (class "Default")
      (node (ref "D238") (pin "1") (pinfunction "A_1") (pintype "passive"))
      (node (ref "S238") (pin "1") (pinfunction "1_1") (pintype "passive"))
    )
    (net (code "56") (name "Net-(D239-A)") (class "Default")
      (node (ref "D239") (pin "1") (pinfunction "A_1") (pintype "passive"))
      (node (ref "S239") (pin "1") (pinfunction "1_1") (pintype "passive"))
    )
    (net (code "57") (name "Net-(D240-A)") (class "Default")
      (node (ref "D240") (pin "1") (pinfunction "A_1") (pintype "passive"))
      (node (ref "S240") (pin "1") (pinfunction "1_1") (pintype "passive"))
    )
    (net (code "58") (name "Net-(D242-A)") (class "Default")
      (node (ref "D242") (pin "1") (pinfunction "A_1") (pintype "passive"))
      (node (ref "S242") (pin "1") (pinfunction "1_1") (pintype "passive"))
    )
    (net (code "59") (name "Net-(D243-A)") (class "Default")
      (node (ref "D243") (pin "1") (pinfunction "A_1") (pintype "passive"))
      (node (ref "S243") (pin "1") (pinfunction "1_1") (pintype "passive"))
    )
    (net (code "60") (name "Net-(D244-A)") (class "Default")
      (node (ref "D244") (pin "1") (pinfunction "A_1") (pintype "passive"))
      (node (ref "S244") (pin "1") (pinfunction "1_1") (pintype "passive"))
    )
    (net (code "61") (name "Net-(D245-A)") (class "Default")
      (node (ref "D245") (pin "1") (pinfunction "A_1") (pintype "passive"))
      (node (ref "S245") (pin "1") (pinfunction "1_1") (pintype "passive"))
    )
    (net (code "62") (name "Net-(D246-A)") (class "Default")
      (node (ref "D246") (pin "1") (pinfunction "A_1") (pintype "passive"))
      (node (ref "S246") (pin "1") (pinfunction "1_1") (pintype "passive"))
    )
    (net (code "63") (name "Net-(D247-A)") (class "Default")
      (node (ref "D247") (pin "1") (pinfunction "A_1") (pintype "passive"))
      (node (ref "S247") (pin "1") (pinfunction "1_1") (pintype "passive"))
    )
    (net (code "64") (name "Net-(D248-A)") (class "Default")
      (node (ref "D248") (pin "1") (pinfunction "A_1") (pintype "passive"))
      (node (ref "S248") (pin "1") (pinfunction "1_1") (pintype "passive"))
    )
    (net (code "65") (name "Net-(D249-A)") (class "Default")
      (node (ref "D249") (pin "1") (pinfunction "A_1") (pintype "passive"))
      (node (ref "S249") (pin "1") (pinfunction "1_1") (pintype "passive"))
    )
    (net (code "66") (name "Net-(D250-A)") (class "Default")
      (node (ref "D250") (pin "1") (pinfunction "A_1") (pintype "passive"))
      (node (ref "S250") (pin "1") (pinfunction "1_1") (pintype "passive"))
    )
    (net (code "67") (name "Net-(D251-A)") (class "Default")
      (node (ref "D251") (pin "1") (pinfunction "A_1") (pintype "passive"))
      (node (ref "S251") (pin "1") (pinfunction "1_1") (pintype "passive"))
    )
    (net (code "68") (name "Net-(D252-A)") (class "Default")
      (node (ref "D252") (pin "1") (pinfunction "A_1") (pintype "passive"))
      (node (ref "S252") (pin "1") (pinfunction "1_1") (pintype "passive"))
    )
    (net (code "69") (name "Net-(D253-A)") (class "Default")
      (node (ref "D253") (pin "1") (pinfunction "A_1") (pintype "passive"))
      (node (ref "S253") (pin "1") (pinfunction "1_1") (pintype "passive"))
    )
    (net (code "70") (name "Net-(D254-A)") (class "Default")
      (node (ref "D254") (pin "1") (pinfunction "A_1") (pintype "passive"))
      (node (ref "S254") (pin "1") (pinfunction "1_1") (pintype "passive"))
    )
    (net (code "71") (name "Net-(D256-A)") (class "Default")
      (node (ref "D256") (pin "1") (pinfunction "A_1") (pintype "passive"))
      (node (ref "S256") (pin "1") (pinfunction "1_1") (pintype "passive"))
    )
    (net (code "72") (name "Net-(D257-A)") (class "Default")
      (node (ref "D257") (pin "1") (pinfunction "A_1") (pintype "passive"))
      (node (ref "S257") (pin "1") (pinfunction "1_1") (pintype "passive"))
    )
    (net (code "73") (name "Net-(D258-A)") (class "Default")
      (node (ref "D258") (pin "1") (pinfunction "A_1") (pintype "passive"))
      (node (ref "S258") (pin "1") (pinfunction "1_1") (pintype "passive"))
    )
    (net (code "74") (name "Net-(D259-A)") (class "Default")
      (node (ref "D259") (pin "1") (pinfunction "A_1") (pintype "passive"))
      (node (ref "S259") (pin "1") (pinfunction "1_1") (pintype "passive"))
    )
    (net (code "75") (name "Net-(D260-A)") (class "Default")
      (node (ref "D260") (pin "1") (pinfunction "A_1") (pintype "passive"))
      (node (ref "S260") (pin "1") (pinfunction "1_1") (pintype "passive"))
    )
    (net (code "76") (name "Net-(D262-A)") (class "Default")
      (node (ref "D262") (pin "1") (pinfunction "A_1") (pintype "passive"))
      (node (ref "S262") (pin "2") (pinfunction "2_2") (pintype "passive"))
    )
    (net (code "77") (name "Net-(D264-A)") (class "Default")
      (node (ref "D264") (pin "1") (pinfunction "A_1") (pintype "passive"))
      (node (ref "S264") (pin "1") (pinfunction "1_1") (pintype "passive"))
    )
    (net (code "78") (name "Net-(D265-A)") (class "Default")
      (node (ref "D265") (pin "1") (pinfunction "A_1") (pintype "passive"))
      (node (ref "S265") (pin "2") (pinfunction "2_2") (pintype "passive"))
    )
    (net (code "79") (name "Net-(D266-A)") (class "Default")
      (node (ref "D266") (pin "1") (pinfunction "A_1") (pintype "passive"))
      (node (ref "S266") (pin "1") (pinfunction "1_1") (pintype "passive"))
    )
    (net (code "80") (name "Net-(D267-A)") (class "Default")
      (node (ref "D267") (pin "1") (pinfunction "A_1") (pintype "passive"))
      (node (ref "S267") (pin "1") (pinfunction "1_1") (pintype "passive"))
    )
    (net (code "81") (name "Net-(D268-A)") (class "Default")
      (node (ref "D268") (pin "1") (pinfunction "A_1") (pintype "passive"))
      (node (ref "S268") (pin "1") (pinfunction "1_1") (pintype "passive"))
    )
    (net (code "82") (name "Net-(D269-A)") (class "Default")
      (node (ref "D269") (pin "1") (pinfunction "A_1") (pintype "passive"))
      (node (ref "S269") (pin "1") (pinfunction "1_1") (pintype "passive"))
    )
    (net (code "83") (name "Net-(D270-A)") (class "Default")
      (node (ref "D270") (pin "1") (pinfunction "A_1") (pintype "passive"))
      (node (ref "S270") (pin "1") (pinfunction "1_1") (pintype "passive"))
    )
  )
)
